# MAX-6566-Adapter_v2_1.net
KiCad netlist of a schematic drawn in EAGLE
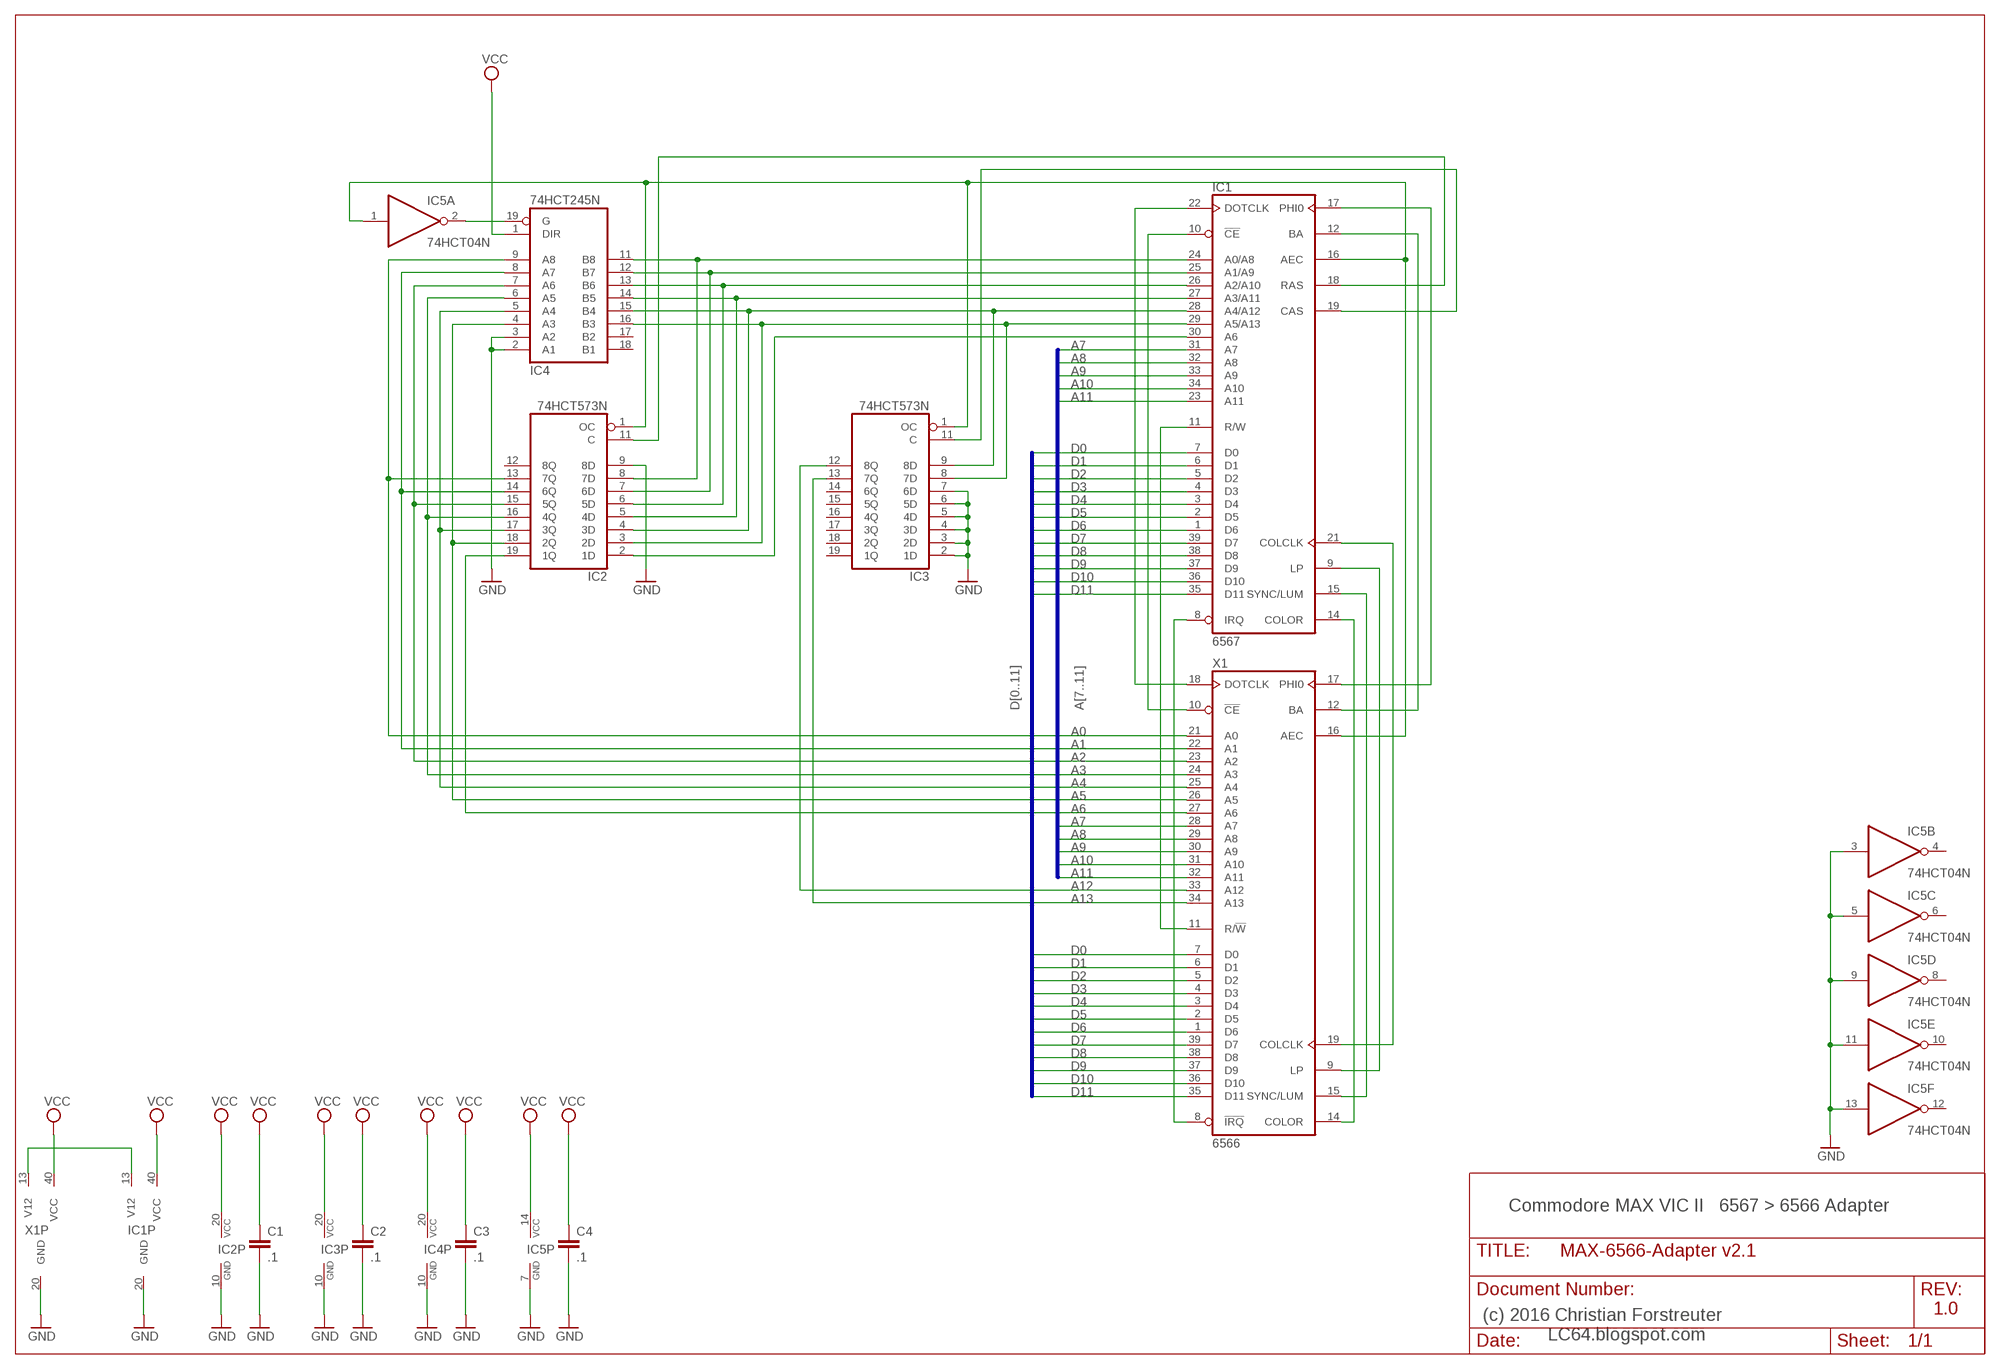
[diagram p0: schematic, sheet 1]

(export (version "E")
  (design (tool "Eeschema 10.0.6"))
  (components
    (comp (ref "C1")
      (value ".1")
      (footprint "eagle-import:C025-024X044")
      (libsource (lib "eagle-import") (part "C-EU025-024X044"))
    )
    (comp (ref "C2")
      (value ".1")
      (footprint "eagle-import:C025-024X044")
      (libsource (lib "eagle-import") (part "C-EU025-024X044"))
    )
    (comp (ref "C3")
      (value ".1")
      (footprint "eagle-import:C025-024X044")
      (libsource (lib "eagle-import") (part "C-EU025-024X044"))
    )
    (comp (ref "C4")
      (value ".1")
      (footprint "eagle-import:C025-024X044")
      (libsource (lib "eagle-import") (part "C-EU025-024X044"))
    )
    (comp (ref "IC1")
      (value "6567")
      (footprint "eagle-import:DIL40-ROUNDPAD")
      (libsource (lib "eagle-import") (part "6569-RP"))
    )
    (comp (ref "IC2")
      (value "74HCT573N")
      (footprint "eagle-import:74XX-EU_DIL20")
      (libsource (lib "eagle-import") (part "74XX-EU_74573NHCT"))
    )
    (comp (ref "IC3")
      (value "74HCT573N")
      (footprint "eagle-import:74XX-EU_DIL20")
      (libsource (lib "eagle-import") (part "74XX-EU_74573NHCT"))
    )
    (comp (ref "IC4")
      (value "74HCT245N")
      (footprint "eagle-import:74XX-EU_DIL20")
      (libsource (lib "eagle-import") (part "74XX-EU_74245NHCT"))
    )
    (comp (ref "IC5")
      (value "74HCT04N")
      (footprint "eagle-import:74XX-EU_DIL14")
      (libsource (lib "eagle-import") (part "74XX-EU_7404NHCT"))
    )
    (comp (ref "X1")
      (value "6566")
      (footprint "eagle-import:DIL40-ROUNDPAD")
      (libsource (lib "eagle-import") (part "6566-RP"))
    )
  )
  (nets
    (net (code "1") (name "/A0") (class "Default")
      (node (ref "IC2") (pin "13") (pinfunction "7Q_13") (pintype "tri_state"))
      (node (ref "IC4") (pin "9") (pinfunction "A8_9") (pintype "bidirectional"))
      (node (ref "X1") (pin "21") (pinfunction "A0_21") (pintype "tri_state"))
    )
    (net (code "2") (name "/A1") (class "Default")
      (node (ref "IC2") (pin "14") (pinfunction "6Q_14") (pintype "tri_state"))
      (node (ref "IC4") (pin "8") (pinfunction "A7_8") (pintype "bidirectional"))
      (node (ref "X1") (pin "22") (pinfunction "A1_22") (pintype "tri_state"))
    )
    (net (code "3") (name "/A2") (class "Default")
      (node (ref "IC2") (pin "15") (pinfunction "5Q_15") (pintype "tri_state"))
      (node (ref "IC4") (pin "7") (pinfunction "A6_7") (pintype "bidirectional"))
      (node (ref "X1") (pin "23") (pinfunction "A2_23") (pintype "tri_state"))
    )
    (net (code "4") (name "/A3") (class "Default")
      (node (ref "IC2") (pin "16") (pinfunction "4Q_16") (pintype "tri_state"))
      (node (ref "IC4") (pin "6") (pinfunction "A5_6") (pintype "bidirectional"))
      (node (ref "X1") (pin "24") (pinfunction "A3_24") (pintype "tri_state"))
    )
    (net (code "5") (name "/A4") (class "Default")
      (node (ref "IC2") (pin "17") (pinfunction "3Q_17") (pintype "tri_state"))
      (node (ref "IC4") (pin "5") (pinfunction "A4_5") (pintype "bidirectional"))
      (node (ref "X1") (pin "25") (pinfunction "A4_25") (pintype "tri_state"))
    )
    (net (code "6") (name "/A5") (class "Default")
      (node (ref "IC2") (pin "18") (pinfunction "2Q_18") (pintype "tri_state"))
      (node (ref "IC4") (pin "4") (pinfunction "A3_4") (pintype "bidirectional"))
      (node (ref "X1") (pin "26") (pinfunction "A5_26") (pintype "tri_state"))
    )
    (net (code "7") (name "/A6") (class "Default")
      (node (ref "IC2") (pin "19") (pinfunction "1Q_19") (pintype "tri_state"))
      (node (ref "X1") (pin "27") (pinfunction "A6_27") (pintype "tri_state"))
    )
    (net (code "8") (name "/A7") (class "Default")
      (node (ref "IC1") (pin "31") (pinfunction "A7_31") (pintype "tri_state"))
      (node (ref "X1") (pin "28") (pinfunction "A7_28") (pintype "tri_state"))
    )
    (net (code "9") (name "/A8") (class "Default")
      (node (ref "IC1") (pin "32") (pinfunction "A8_32") (pintype "tri_state"))
      (node (ref "X1") (pin "29") (pinfunction "A8_29") (pintype "tri_state"))
    )
    (net (code "10") (name "/A9") (class "Default")
      (node (ref "IC1") (pin "33") (pinfunction "A9_33") (pintype "tri_state"))
      (node (ref "X1") (pin "30") (pinfunction "A9_30") (pintype "tri_state"))
    )
    (net (code "11") (name "/A10") (class "Default")
      (node (ref "IC1") (pin "34") (pinfunction "A10_34") (pintype "tri_state"))
      (node (ref "X1") (pin "31") (pinfunction "A10_31") (pintype "tri_state"))
    )
    (net (code "12") (name "/A11") (class "Default")
      (node (ref "IC1") (pin "23") (pinfunction "A11_23") (pintype "tri_state"))
      (node (ref "X1") (pin "32") (pinfunction "A11_32") (pintype "tri_state"))
    )
    (net (code "13") (name "/A12") (class "Default")
      (node (ref "IC3") (pin "12") (pinfunction "8Q_12") (pintype "tri_state"))
      (node (ref "X1") (pin "33") (pinfunction "A12_33") (pintype "tri_state"))
    )
    (net (code "14") (name "/A13") (class "Default")
      (node (ref "IC3") (pin "13") (pinfunction "7Q_13") (pintype "tri_state"))
      (node (ref "X1") (pin "34") (pinfunction "A13_34") (pintype "tri_state"))
    )
    (net (code "16") (name "/D0") (class "Default")
      (node (ref "IC1") (pin "7") (pinfunction "D0_7") (pintype "tri_state"))
      (node (ref "X1") (pin "7") (pinfunction "D0_7") (pintype "tri_state"))
    )
    (net (code "17") (name "/D1") (class "Default")
      (node (ref "IC1") (pin "6") (pinfunction "D1_6") (pintype "tri_state"))
      (node (ref "X1") (pin "6") (pinfunction "D1_6") (pintype "tri_state"))
    )
    (net (code "18") (name "/D2") (class "Default")
      (node (ref "IC1") (pin "5") (pinfunction "D2_5") (pintype "tri_state"))
      (node (ref "X1") (pin "5") (pinfunction "D2_5") (pintype "tri_state"))
    )
    (net (code "19") (name "/D3") (class "Default")
      (node (ref "IC1") (pin "4") (pinfunction "D3_4") (pintype "tri_state"))
      (node (ref "X1") (pin "4") (pinfunction "D3_4") (pintype "tri_state"))
    )
    (net (code "20") (name "/D4") (class "Default")
      (node (ref "IC1") (pin "3") (pinfunction "D4_3") (pintype "tri_state"))
      (node (ref "X1") (pin "3") (pinfunction "D4_3") (pintype "tri_state"))
    )
    (net (code "21") (name "/D5") (class "Default")
      (node (ref "IC1") (pin "2") (pinfunction "D5_2") (pintype "tri_state"))
      (node (ref "X1") (pin "2") (pinfunction "D5_2") (pintype "tri_state"))
    )
    (net (code "22") (name "/D6") (class "Default")
      (node (ref "IC1") (pin "1") (pinfunction "D6_1") (pintype "tri_state"))
      (node (ref "X1") (pin "1") (pinfunction "D6_1") (pintype "tri_state"))
    )
    (net (code "23") (name "/D7") (class "Default")
      (node (ref "IC1") (pin "39") (pinfunction "D7_39") (pintype "tri_state"))
      (node (ref "X1") (pin "39") (pinfunction "D7_39") (pintype "tri_state"))
    )
    (net (code "24") (name "/D8") (class "Default")
      (node (ref "IC1") (pin "38") (pinfunction "D8_38") (pintype "tri_state"))
      (node (ref "X1") (pin "38") (pinfunction "D8_38") (pintype "tri_state"))
    )
    (net (code "25") (name "/D9") (class "Default")
      (node (ref "IC1") (pin "37") (pinfunction "D9_37") (pintype "tri_state"))
      (node (ref "X1") (pin "37") (pinfunction "D9_37") (pintype "tri_state"))
    )
    (net (code "26") (name "/D10") (class "Default")
      (node (ref "IC1") (pin "36") (pinfunction "D10_36") (pintype "tri_state"))
      (node (ref "X1") (pin "36") (pinfunction "D10_36") (pintype "tri_state"))
    )
    (net (code "27") (name "/D11") (class "Default")
      (node (ref "IC1") (pin "35") (pinfunction "D11_35") (pintype "tri_state"))
      (node (ref "X1") (pin "35") (pinfunction "D11_35") (pintype "tri_state"))
    )
    (net (code "29") (name "GND") (class "Default")
      (node (ref "C1") (pin "2") (pinfunction "2_2") (pintype "passive"))
      (node (ref "C2") (pin "2") (pinfunction "2_2") (pintype "passive"))
      (node (ref "C3") (pin "2") (pinfunction "2_2") (pintype "passive"))
      (node (ref "C4") (pin "2") (pinfunction "2_2") (pintype "passive"))
      (node (ref "IC1") (pin "20") (pinfunction "GND_20") (pintype "power_in"))
      (node (ref "IC2") (pin "10") (pinfunction "GND_10") (pintype "power_in"))
      (node (ref "IC2") (pin "9") (pinfunction "8D_9") (pintype "input"))
      (node (ref "IC3") (pin "10") (pinfunction "GND_10") (pintype "power_in"))
      (node (ref "IC3") (pin "2") (pinfunction "1D_2") (pintype "input"))
      (node (ref "IC3") (pin "3") (pinfunction "2D_3") (pintype "input"))
      (node (ref "IC3") (pin "4") (pinfunction "3D_4") (pintype "input"))
      (node (ref "IC3") (pin "5") (pinfunction "4D_5") (pintype "input"))
      (node (ref "IC3") (pin "6") (pinfunction "5D_6") (pintype "input"))
      (node (ref "IC3") (pin "7") (pinfunction "6D_7") (pintype "input"))
      (node (ref "IC4") (pin "10") (pinfunction "GND_10") (pintype "power_in"))
      (node (ref "IC4") (pin "2") (pinfunction "A1_2") (pintype "bidirectional"))
      (node (ref "IC4") (pin "3") (pinfunction "A2_3") (pintype "bidirectional"))
      (node (ref "IC5") (pin "11") (pinfunction "I_11") (pintype "input"))
      (node (ref "IC5") (pin "13") (pinfunction "I_13") (pintype "input"))
      (node (ref "IC5") (pin "3") (pinfunction "I_3") (pintype "input"))
      (node (ref "IC5") (pin "5") (pinfunction "I_5") (pintype "input"))
      (node (ref "IC5") (pin "7") (pinfunction "GND_7") (pintype "power_in"))
      (node (ref "IC5") (pin "9") (pinfunction "I_9") (pintype "input"))
      (node (ref "X1") (pin "20") (pinfunction "GND_20") (pintype "power_in"))
    )
    (net (code "30") (name "Net-(IC1A-A0{slash}A8)") (class "Default")
      (node (ref "IC1") (pin "24") (pinfunction "A0/A8_24") (pintype "tri_state"))
      (node (ref "IC2") (pin "8") (pinfunction "7D_8") (pintype "input"))
      (node (ref "IC4") (pin "11") (pinfunction "B8_11") (pintype "bidirectional"))
    )
    (net (code "31") (name "Net-(IC1A-A1{slash}A9)") (class "Default")
      (node (ref "IC1") (pin "25") (pinfunction "A1/A9_25") (pintype "tri_state"))
      (node (ref "IC2") (pin "7") (pinfunction "6D_7") (pintype "input"))
      (node (ref "IC4") (pin "12") (pinfunction "B7_12") (pintype "bidirectional"))
    )
    (net (code "32") (name "Net-(IC1A-A2{slash}A10)") (class "Default")
      (node (ref "IC1") (pin "26") (pinfunction "A2/A10_26") (pintype "tri_state"))
      (node (ref "IC2") (pin "6") (pinfunction "5D_6") (pintype "input"))
      (node (ref "IC4") (pin "13") (pinfunction "B6_13") (pintype "bidirectional"))
    )
    (net (code "33") (name "Net-(IC1A-A3{slash}A11)") (class "Default")
      (node (ref "IC1") (pin "27") (pinfunction "A3/A11_27") (pintype "tri_state"))
      (node (ref "IC2") (pin "5") (pinfunction "4D_5") (pintype "input"))
      (node (ref "IC4") (pin "14") (pinfunction "B5_14") (pintype "bidirectional"))
    )
    (net (code "34") (name "Net-(IC1A-A4{slash}A12)") (class "Default")
      (node (ref "IC1") (pin "28") (pinfunction "A4/A12_28") (pintype "tri_state"))
      (node (ref "IC2") (pin "4") (pinfunction "3D_4") (pintype "input"))
      (node (ref "IC3") (pin "9") (pinfunction "8D_9") (pintype "input"))
      (node (ref "IC4") (pin "15") (pinfunction "B4_15") (pintype "bidirectional"))
    )
    (net (code "35") (name "Net-(IC1A-A5{slash}A13)") (class "Default")
      (node (ref "IC1") (pin "29") (pinfunction "A5/A13_29") (pintype "tri_state"))
      (node (ref "IC2") (pin "3") (pinfunction "2D_3") (pintype "input"))
      (node (ref "IC3") (pin "8") (pinfunction "7D_8") (pintype "input"))
      (node (ref "IC4") (pin "16") (pinfunction "B3_16") (pintype "bidirectional"))
    )
    (net (code "36") (name "Net-(IC1A-A6)") (class "Default")
      (node (ref "IC1") (pin "30") (pinfunction "A6_30") (pintype "tri_state"))
      (node (ref "IC2") (pin "2") (pinfunction "1D_2") (pintype "input"))
    )
    (net (code "37") (name "Net-(IC1A-AEC)") (class "Default")
      (node (ref "IC1") (pin "16") (pinfunction "AEC_16") (pintype "output"))
      (node (ref "IC2") (pin "1") (pinfunction "OC_1") (pintype "input"))
      (node (ref "IC3") (pin "1") (pinfunction "OC_1") (pintype "input"))
      (node (ref "IC5") (pin "1") (pinfunction "I_1") (pintype "input"))
      (node (ref "X1") (pin "16") (pinfunction "AEC_16") (pintype "output"))
    )
    (net (code "38") (name "Net-(IC1A-BA)") (class "Default")
      (node (ref "IC1") (pin "12") (pinfunction "BA_12") (pintype "output"))
      (node (ref "X1") (pin "12") (pinfunction "BA_12") (pintype "output"))
    )
    (net (code "39") (name "Net-(IC1A-CAS)") (class "Default")
      (node (ref "IC1") (pin "19") (pinfunction "CAS_19") (pintype "output"))
      (node (ref "IC3") (pin "11") (pinfunction "C_11") (pintype "input"))
    )
    (net (code "40") (name "Net-(IC1A-COLCLK)") (class "Default")
      (node (ref "IC1") (pin "21") (pinfunction "COLCLK_21") (pintype "input"))
      (node (ref "X1") (pin "19") (pinfunction "COLCLK_19") (pintype "input"))
    )
    (net (code "41") (name "Net-(IC1A-COLOR)") (class "Default")
      (node (ref "IC1") (pin "14") (pinfunction "COLOR_14") (pintype "output"))
      (node (ref "X1") (pin "14") (pinfunction "COLOR_14") (pintype "output"))
    )
    (net (code "42") (name "Net-(IC1A-DOTCLK)") (class "Default")
      (node (ref "IC1") (pin "22") (pinfunction "DOTCLK_22") (pintype "input"))
      (node (ref "X1") (pin "18") (pinfunction "DOTCLK_18") (pintype "input"))
    )
    (net (code "43") (name "Net-(IC1A-IRQ)") (class "Default")
      (node (ref "IC1") (pin "8") (pinfunction "IRQ_8") (pintype "open_collector"))
      (node (ref "X1") (pin "8") (pinfunction "~{IRQ}_8") (pintype "open_collector"))
    )
    (net (code "44") (name "Net-(IC1A-LP)") (class "Default")
      (node (ref "IC1") (pin "9") (pinfunction "LP_9") (pintype "input"))
      (node (ref "X1") (pin "9") (pinfunction "LP_9") (pintype "input"))
    )
    (net (code "45") (name "Net-(IC1A-PHI0)") (class "Default")
      (node (ref "IC1") (pin "17") (pinfunction "PHI0_17") (pintype "output"))
      (node (ref "X1") (pin "17") (pinfunction "PHI0_17") (pintype "output"))
    )
    (net (code "46") (name "Net-(IC1A-RAS)") (class "Default")
      (node (ref "IC1") (pin "18") (pinfunction "RAS_18") (pintype "output"))
      (node (ref "IC2") (pin "11") (pinfunction "C_11") (pintype "input"))
    )
    (net (code "47") (name "Net-(IC1A-R{slash}W)") (class "Default")
      (node (ref "IC1") (pin "11") (pinfunction "R/W_11") (pintype "input"))
      (node (ref "X1") (pin "11") (pinfunction "R/~{W}_11") (pintype "input"))
    )
    (net (code "48") (name "Net-(IC1A-SYNC{slash}LUM)") (class "Default")
      (node (ref "IC1") (pin "15") (pinfunction "SYNC/LUM_15") (pintype "output"))
      (node (ref "X1") (pin "15") (pinfunction "SYNC/LUM_15") (pintype "output"))
    )
    (net (code "49") (name "Net-(IC1A-~{CE})") (class "Default")
      (node (ref "IC1") (pin "10") (pinfunction "~{CE}_10") (pintype "input"))
      (node (ref "X1") (pin "10") (pinfunction "~{CE}_10") (pintype "input"))
    )
    (net (code "50") (name "Net-(IC1B-V12)") (class "Default")
      (node (ref "IC1") (pin "13") (pinfunction "V12_13") (pintype "power_in"))
      (node (ref "X1") (pin "13") (pinfunction "V12_13") (pintype "power_in"))
    )
    (net (code "51") (name "Net-(IC4A-G)") (class "Default")
      (node (ref "IC4") (pin "19") (pinfunction "G_19") (pintype "input"))
      (node (ref "IC5") (pin "2") (pinfunction "O_2") (pintype "output"))
    )
    (net (code "52") (name "VCC") (class "Default")
      (node (ref "C1") (pin "1") (pinfunction "1_1") (pintype "passive"))
      (node (ref "C2") (pin "1") (pinfunction "1_1") (pintype "passive"))
      (node (ref "C3") (pin "1") (pinfunction "1_1") (pintype "passive"))
      (node (ref "C4") (pin "1") (pinfunction "1_1") (pintype "passive"))
      (node (ref "IC1") (pin "40") (pinfunction "VCC_40") (pintype "power_in"))
      (node (ref "IC2") (pin "20") (pinfunction "VCC_20") (pintype "power_in"))
      (node (ref "IC3") (pin "20") (pinfunction "VCC_20") (pintype "power_in"))
      (node (ref "IC4") (pin "1") (pinfunction "DIR_1") (pintype "input"))
      (node (ref "IC4") (pin "20") (pinfunction "VCC_20") (pintype "power_in"))
      (node (ref "IC5") (pin "14") (pinfunction "VCC_14") (pintype "power_in"))
      (node (ref "X1") (pin "40") (pinfunction "VCC_40") (pintype "power_in"))
    )
    (net (code "53") (name "unconnected-(IC2A-8Q-Pad12)") (class "Default")
      (node (ref "IC2") (pin "12") (pinfunction "8Q_12") (pintype "tri_state"))
    )
    (net (code "54") (name "unconnected-(IC3A-1Q-Pad19)") (class "Default")
      (node (ref "IC3") (pin "19") (pinfunction "1Q_19") (pintype "tri_state"))
    )
    (net (code "55") (name "unconnected-(IC3A-2Q-Pad18)") (class "Default")
      (node (ref "IC3") (pin "18") (pinfunction "2Q_18") (pintype "tri_state"))
    )
    (net (code "56") (name "unconnected-(IC3A-3Q-Pad17)") (class "Default")
      (node (ref "IC3") (pin "17") (pinfunction "3Q_17") (pintype "tri_state"))
    )
    (net (code "57") (name "unconnected-(IC3A-4Q-Pad16)") (class "Default")
      (node (ref "IC3") (pin "16") (pinfunction "4Q_16") (pintype "tri_state"))
    )
    (net (code "58") (name "unconnected-(IC3A-5Q-Pad15)") (class "Default")
      (node (ref "IC3") (pin "15") (pinfunction "5Q_15") (pintype "tri_state"))
    )
    (net (code "59") (name "unconnected-(IC3A-6Q-Pad14)") (class "Default")
      (node (ref "IC3") (pin "14") (pinfunction "6Q_14") (pintype "tri_state"))
    )
    (net (code "60") (name "unconnected-(IC4A-B1-Pad18)") (class "Default")
      (node (ref "IC4") (pin "18") (pinfunction "B1_18") (pintype "bidirectional"))
    )
    (net (code "61") (name "unconnected-(IC4A-B2-Pad17)") (class "Default")
      (node (ref "IC4") (pin "17") (pinfunction "B2_17") (pintype "bidirectional"))
    )
    (net (code "62") (name "unconnected-(IC5B-O-Pad4)") (class "Default")
      (node (ref "IC5") (pin "4") (pinfunction "O_4") (pintype "output"))
    )
    (net (code "63") (name "unconnected-(IC5C-O-Pad6)") (class "Default")
      (node (ref "IC5") (pin "6") (pinfunction "O_6") (pintype "output"))
    )
    (net (code "64") (name "unconnected-(IC5D-O-Pad8)") (class "Default")
      (node (ref "IC5") (pin "8") (pinfunction "O_8") (pintype "output"))
    )
    (net (code "65") (name "unconnected-(IC5E-O-Pad10)") (class "Default")
      (node (ref "IC5") (pin "10") (pinfunction "O_10") (pintype "output"))
    )
    (net (code "66") (name "unconnected-(IC5F-O-Pad12)") (class "Default")
      (node (ref "IC5") (pin "12") (pinfunction "O_12") (pintype "output"))
    )
  )
)
